# Schematic.net
KiCad netlist of a schematic drawn in Altium Designer
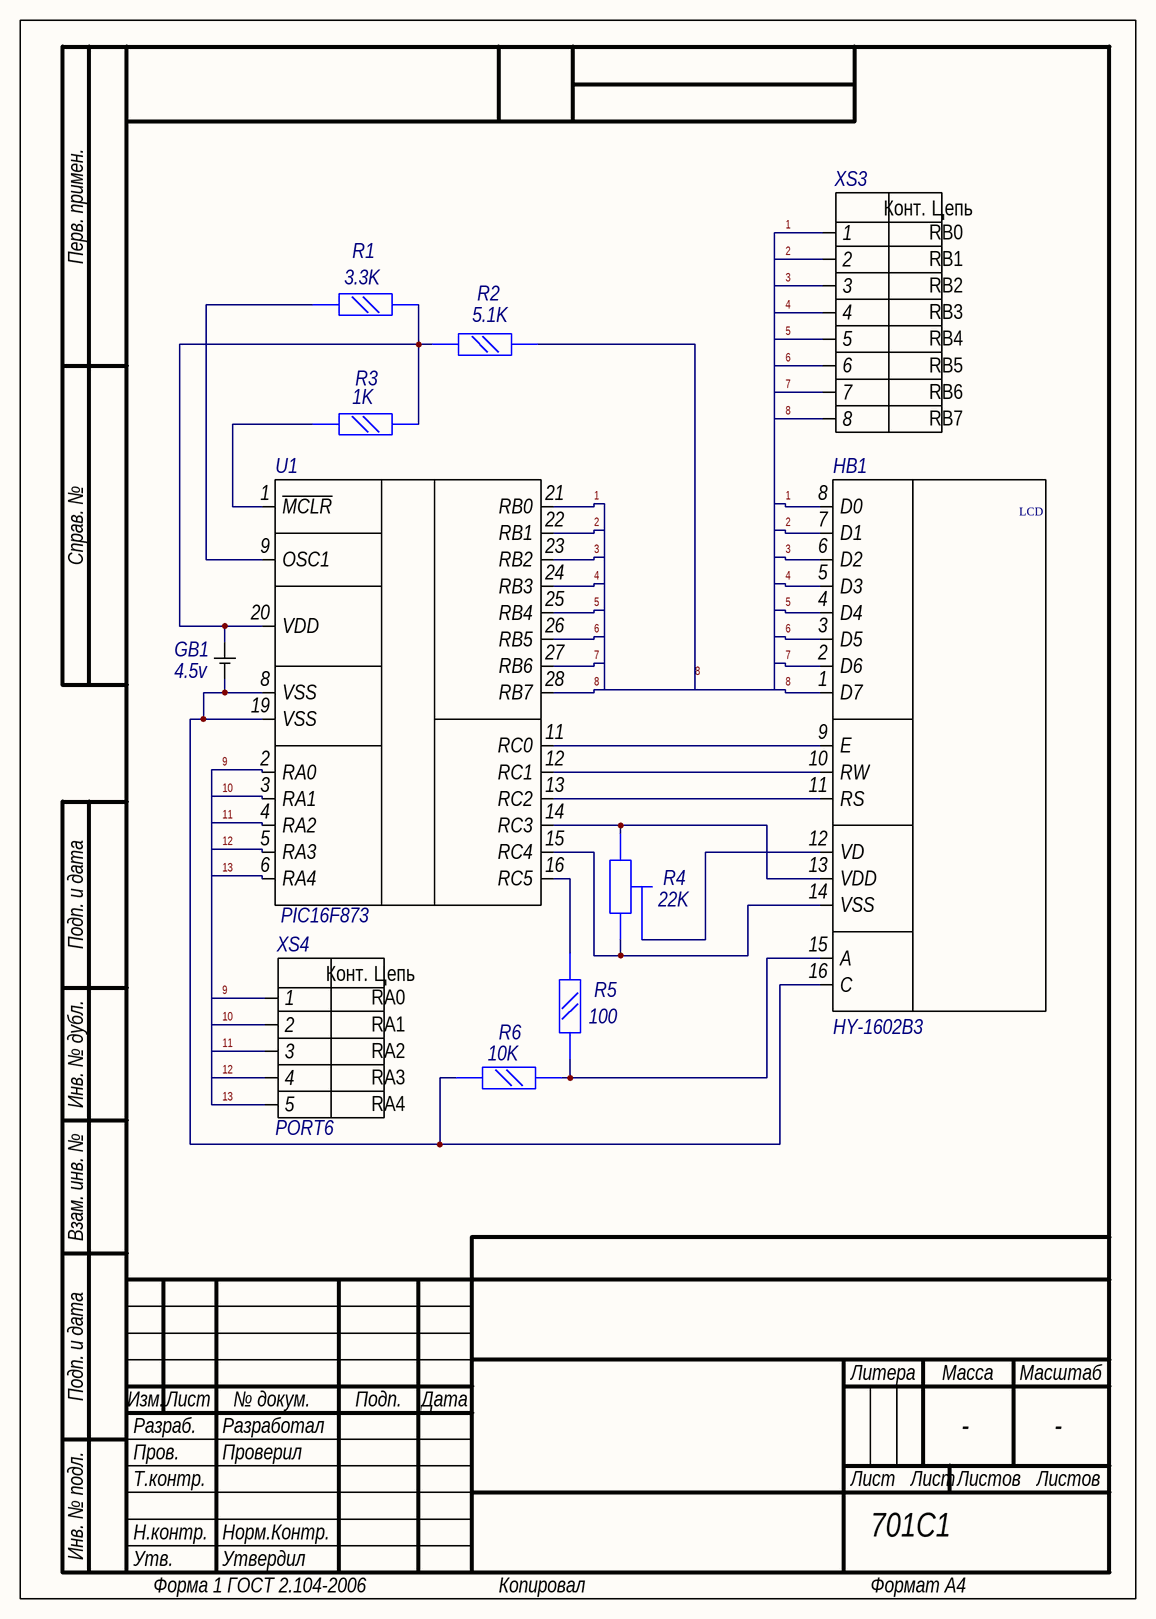
[diagram p0: Schematic.SchDoc]

(export (version "E")
  (design (tool "Eeschema 10.0.6"))
  (components
    (comp (ref "GB1") (value "4.5v") (footprint "XS2holes") (libsource (lib "Schlib1") (part "BAT")))
    (comp (ref "HB1")
      (value "HY-1602B3")
      (footprint "lcd-screen")
      (libsource (lib "Schlib1") (part "HY-1602B3"))
    )
    (comp (ref "R1")
      (value "3.3K")
      (footprint "R1206")
      (fields (field (name "PUBLISHER") "Andrew Danich"))
      (libsource (lib "Resistor GOST") (part "Resistor_0,125W"))
    )
    (comp (ref "R2")
      (value "5.1K")
      (footprint "R1206")
      (fields (field (name "PUBLISHER") "Andrew Danich"))
      (libsource (lib "Resistor GOST") (part "Resistor_0,125W"))
    )
    (comp (ref "R3")
      (value "1K")
      (footprint "R1206")
      (fields (field (name "PUBLISHER") "Andrew Danich"))
      (libsource (lib "Resistor GOST") (part "Resistor_0,125W"))
    )
    (comp (ref "R4")
      (value "22K")
      (footprint "SH-655MCL")
      (fields (field (name "PUBLISHER") "Andrew Danich"))
      (libsource (lib "Resistor GOST") (part "Resistor-Trimmer-1"))
    )
    (comp (ref "R5")
      (value "100")
      (footprint "R1206")
      (fields (field (name "PUBLISHER") "Andrew Danich"))
      (libsource (lib "Resistor GOST") (part "Resistor_0,125W"))
    )
    (comp (ref "R6")
      (value "10K")
      (footprint "R1206")
      (fields (field (name "PUBLISHER") "Andrew Danich"))
      (libsource (lib "Resistor GOST") (part "Resistor_0,125W"))
    )
    (comp (ref "U1") (value "PIC16F873") (footprint "QFP44") (libsource (lib "Schlib1") (part "PIC16F873")))
    (comp (ref "XS3") (value "PORT8") (footprint "XS8HOLES") (libsource (lib "Schlib1") (part "PORT8")))
    (comp (ref "XS4") (value "PORT6") (footprint "XS5HOLES") (libsource (lib "Schlib1") (part "PORT6")))
  )
  (nets
    (net (code "1") (name "/1") (class "Default")
      (node (ref "HB1") (pin "8") (pinfunction "D0_8") (pintype "passive"))
      (node (ref "U1") (pin "21") (pinfunction "RB0_21") (pintype "passive"))
      (node (ref "XS3") (pin "1") (pinfunction "1_1") (pintype "passive"))
    )
    (net (code "2") (name "/2") (class "Default")
      (node (ref "HB1") (pin "7") (pinfunction "D1_7") (pintype "passive"))
      (node (ref "U1") (pin "22") (pinfunction "RB1_22") (pintype "passive"))
      (node (ref "XS3") (pin "2") (pinfunction "2_2") (pintype "passive"))
    )
    (net (code "3") (name "/3") (class "Default")
      (node (ref "HB1") (pin "6") (pinfunction "D2_6") (pintype "passive"))
      (node (ref "U1") (pin "23") (pinfunction "RB2_23") (pintype "passive"))
      (node (ref "XS3") (pin "3") (pinfunction "3_3") (pintype "passive"))
    )
    (net (code "4") (name "/4") (class "Default")
      (node (ref "HB1") (pin "5") (pinfunction "D3_5") (pintype "passive"))
      (node (ref "U1") (pin "24") (pinfunction "RB3_24") (pintype "passive"))
      (node (ref "XS3") (pin "4") (pinfunction "4_4") (pintype "passive"))
    )
    (net (code "5") (name "/5") (class "Default")
      (node (ref "HB1") (pin "4") (pinfunction "D4_4") (pintype "passive"))
      (node (ref "U1") (pin "25") (pinfunction "RB4_25") (pintype "passive"))
      (node (ref "XS3") (pin "5") (pinfunction "5_5") (pintype "passive"))
    )
    (net (code "6") (name "/6") (class "Default")
      (node (ref "HB1") (pin "3") (pinfunction "D5_3") (pintype "passive"))
      (node (ref "U1") (pin "26") (pinfunction "RB5_26") (pintype "passive"))
      (node (ref "XS3") (pin "6") (pinfunction "6_6") (pintype "passive"))
    )
    (net (code "7") (name "/7") (class "Default")
      (node (ref "HB1") (pin "2") (pinfunction "D6_2") (pintype "passive"))
      (node (ref "U1") (pin "27") (pinfunction "RB6_27") (pintype "passive"))
      (node (ref "XS3") (pin "7") (pinfunction "7_7") (pintype "passive"))
    )
    (net (code "8") (name "/8") (class "Default")
      (node (ref "HB1") (pin "1") (pinfunction "D7_1") (pintype "passive"))
      (node (ref "R2") (pin "2") (pinfunction "2_2") (pintype "passive"))
      (node (ref "U1") (pin "28") (pinfunction "RB7_28") (pintype "passive"))
      (node (ref "XS3") (pin "8") (pinfunction "8_8") (pintype "passive"))
    )
    (net (code "9") (name "/9") (class "Default")
      (node (ref "U1") (pin "2") (pinfunction "RA0_2") (pintype "passive"))
      (node (ref "XS4") (pin "1") (pinfunction "1_1") (pintype "passive"))
    )
    (net (code "10") (name "/10") (class "Default")
      (node (ref "U1") (pin "3") (pinfunction "RA1_3") (pintype "passive"))
      (node (ref "XS4") (pin "2") (pinfunction "2_2") (pintype "passive"))
    )
    (net (code "11") (name "/11") (class "Default")
      (node (ref "U1") (pin "4") (pinfunction "RA2_4") (pintype "passive"))
      (node (ref "XS4") (pin "3") (pinfunction "3_3") (pintype "passive"))
    )
    (net (code "12") (name "/12") (class "Default")
      (node (ref "U1") (pin "5") (pinfunction "RA3_5") (pintype "passive"))
      (node (ref "XS4") (pin "4") (pinfunction "4_4") (pintype "passive"))
    )
    (net (code "13") (name "/13") (class "Default")
      (node (ref "U1") (pin "6") (pinfunction "RA4_6") (pintype "passive"))
      (node (ref "XS4") (pin "5") (pinfunction "5_5") (pintype "passive"))
    )
    (net (code "14") (name "Net-(HB1-A)") (class "Default")
      (node (ref "HB1") (pin "15") (pinfunction "A_15") (pintype "passive"))
      (node (ref "R5") (pin "1") (pinfunction "1_1") (pintype "passive"))
      (node (ref "R6") (pin "1") (pinfunction "1_1") (pintype "passive"))
    )
    (net (code "15") (name "Net-(HB1-C)") (class "Default")
      (node (ref "GB1") (pin "2") (pintype "passive"))
      (node (ref "HB1") (pin "16") (pinfunction "C_16") (pintype "passive"))
      (node (ref "R6") (pin "2") (pinfunction "2_2") (pintype "passive"))
      (node (ref "U1") (pin "19") (pinfunction "VSS_19") (pintype "passive"))
      (node (ref "U1") (pin "8") (pinfunction "VSS_8") (pintype "passive"))
    )
    (net (code "16") (name "Net-(HB1-E)") (class "Default")
      (node (ref "HB1") (pin "9") (pinfunction "E_9") (pintype "passive"))
      (node (ref "U1") (pin "11") (pinfunction "RC0_11") (pintype "passive"))
    )
    (net (code "17") (name "Net-(HB1-RS)") (class "Default")
      (node (ref "HB1") (pin "11") (pinfunction "RS_11") (pintype "passive"))
      (node (ref "U1") (pin "13") (pinfunction "RC2_13") (pintype "passive"))
    )
    (net (code "18") (name "Net-(HB1-RW)") (class "Default")
      (node (ref "HB1") (pin "10") (pinfunction "RW_10") (pintype "passive"))
      (node (ref "U1") (pin "12") (pinfunction "RC1_12") (pintype "passive"))
    )
    (net (code "19") (name "Net-(HB1-VD)") (class "Default")
      (node (ref "HB1") (pin "12") (pinfunction "VD_12") (pintype "passive"))
      (node (ref "R4") (pin "2") (pinfunction "2_2") (pintype "passive"))
    )
    (net (code "20") (name "Net-(HB1-VDD)") (class "Default")
      (node (ref "HB1") (pin "13") (pinfunction "VDD_13") (pintype "passive"))
      (node (ref "R4") (pin "3") (pinfunction "3_3") (pintype "passive"))
      (node (ref "U1") (pin "14") (pinfunction "RC3_14") (pintype "passive"))
    )
    (net (code "21") (name "Net-(HB1-VSS)") (class "Default")
      (node (ref "HB1") (pin "14") (pinfunction "VSS_14") (pintype "passive"))
      (node (ref "R4") (pin "1") (pinfunction "1_1") (pintype "passive"))
      (node (ref "U1") (pin "15") (pinfunction "RC4_15") (pintype "passive"))
    )
    (net (code "22") (name "Net-(U1-OSC1)") (class "Default")
      (node (ref "R1") (pin "1") (pinfunction "1_1") (pintype "passive"))
      (node (ref "U1") (pin "9") (pinfunction "OSC1_9") (pintype "passive"))
    )
    (net (code "23") (name "Net-(U1-RC5)") (class "Default")
      (node (ref "R5") (pin "2") (pinfunction "2_2") (pintype "passive"))
      (node (ref "U1") (pin "16") (pinfunction "RC5_16") (pintype "passive"))
    )
    (net (code "24") (name "Net-(U1-VDD)") (class "Default")
      (node (ref "GB1") (pin "1") (pintype "passive"))
      (node (ref "R1") (pin "2") (pinfunction "2_2") (pintype "passive"))
      (node (ref "R2") (pin "1") (pinfunction "1_1") (pintype "passive"))
      (node (ref "R3") (pin "2") (pinfunction "2_2") (pintype "passive"))
      (node (ref "U1") (pin "20") (pinfunction "VDD_20") (pintype "passive"))
    )
    (net (code "25") (name "Net-(U1-~{MCLR})") (class "Default")
      (node (ref "R3") (pin "1") (pinfunction "1_1") (pintype "passive"))
      (node (ref "U1") (pin "1") (pinfunction "~{MCLR}_1") (pintype "passive"))
    )
  )
)
